# Foot_Contact_Switch_2020-11-27_13-26-25.net
KiCad netlist of a schematic drawn in EasyEDA
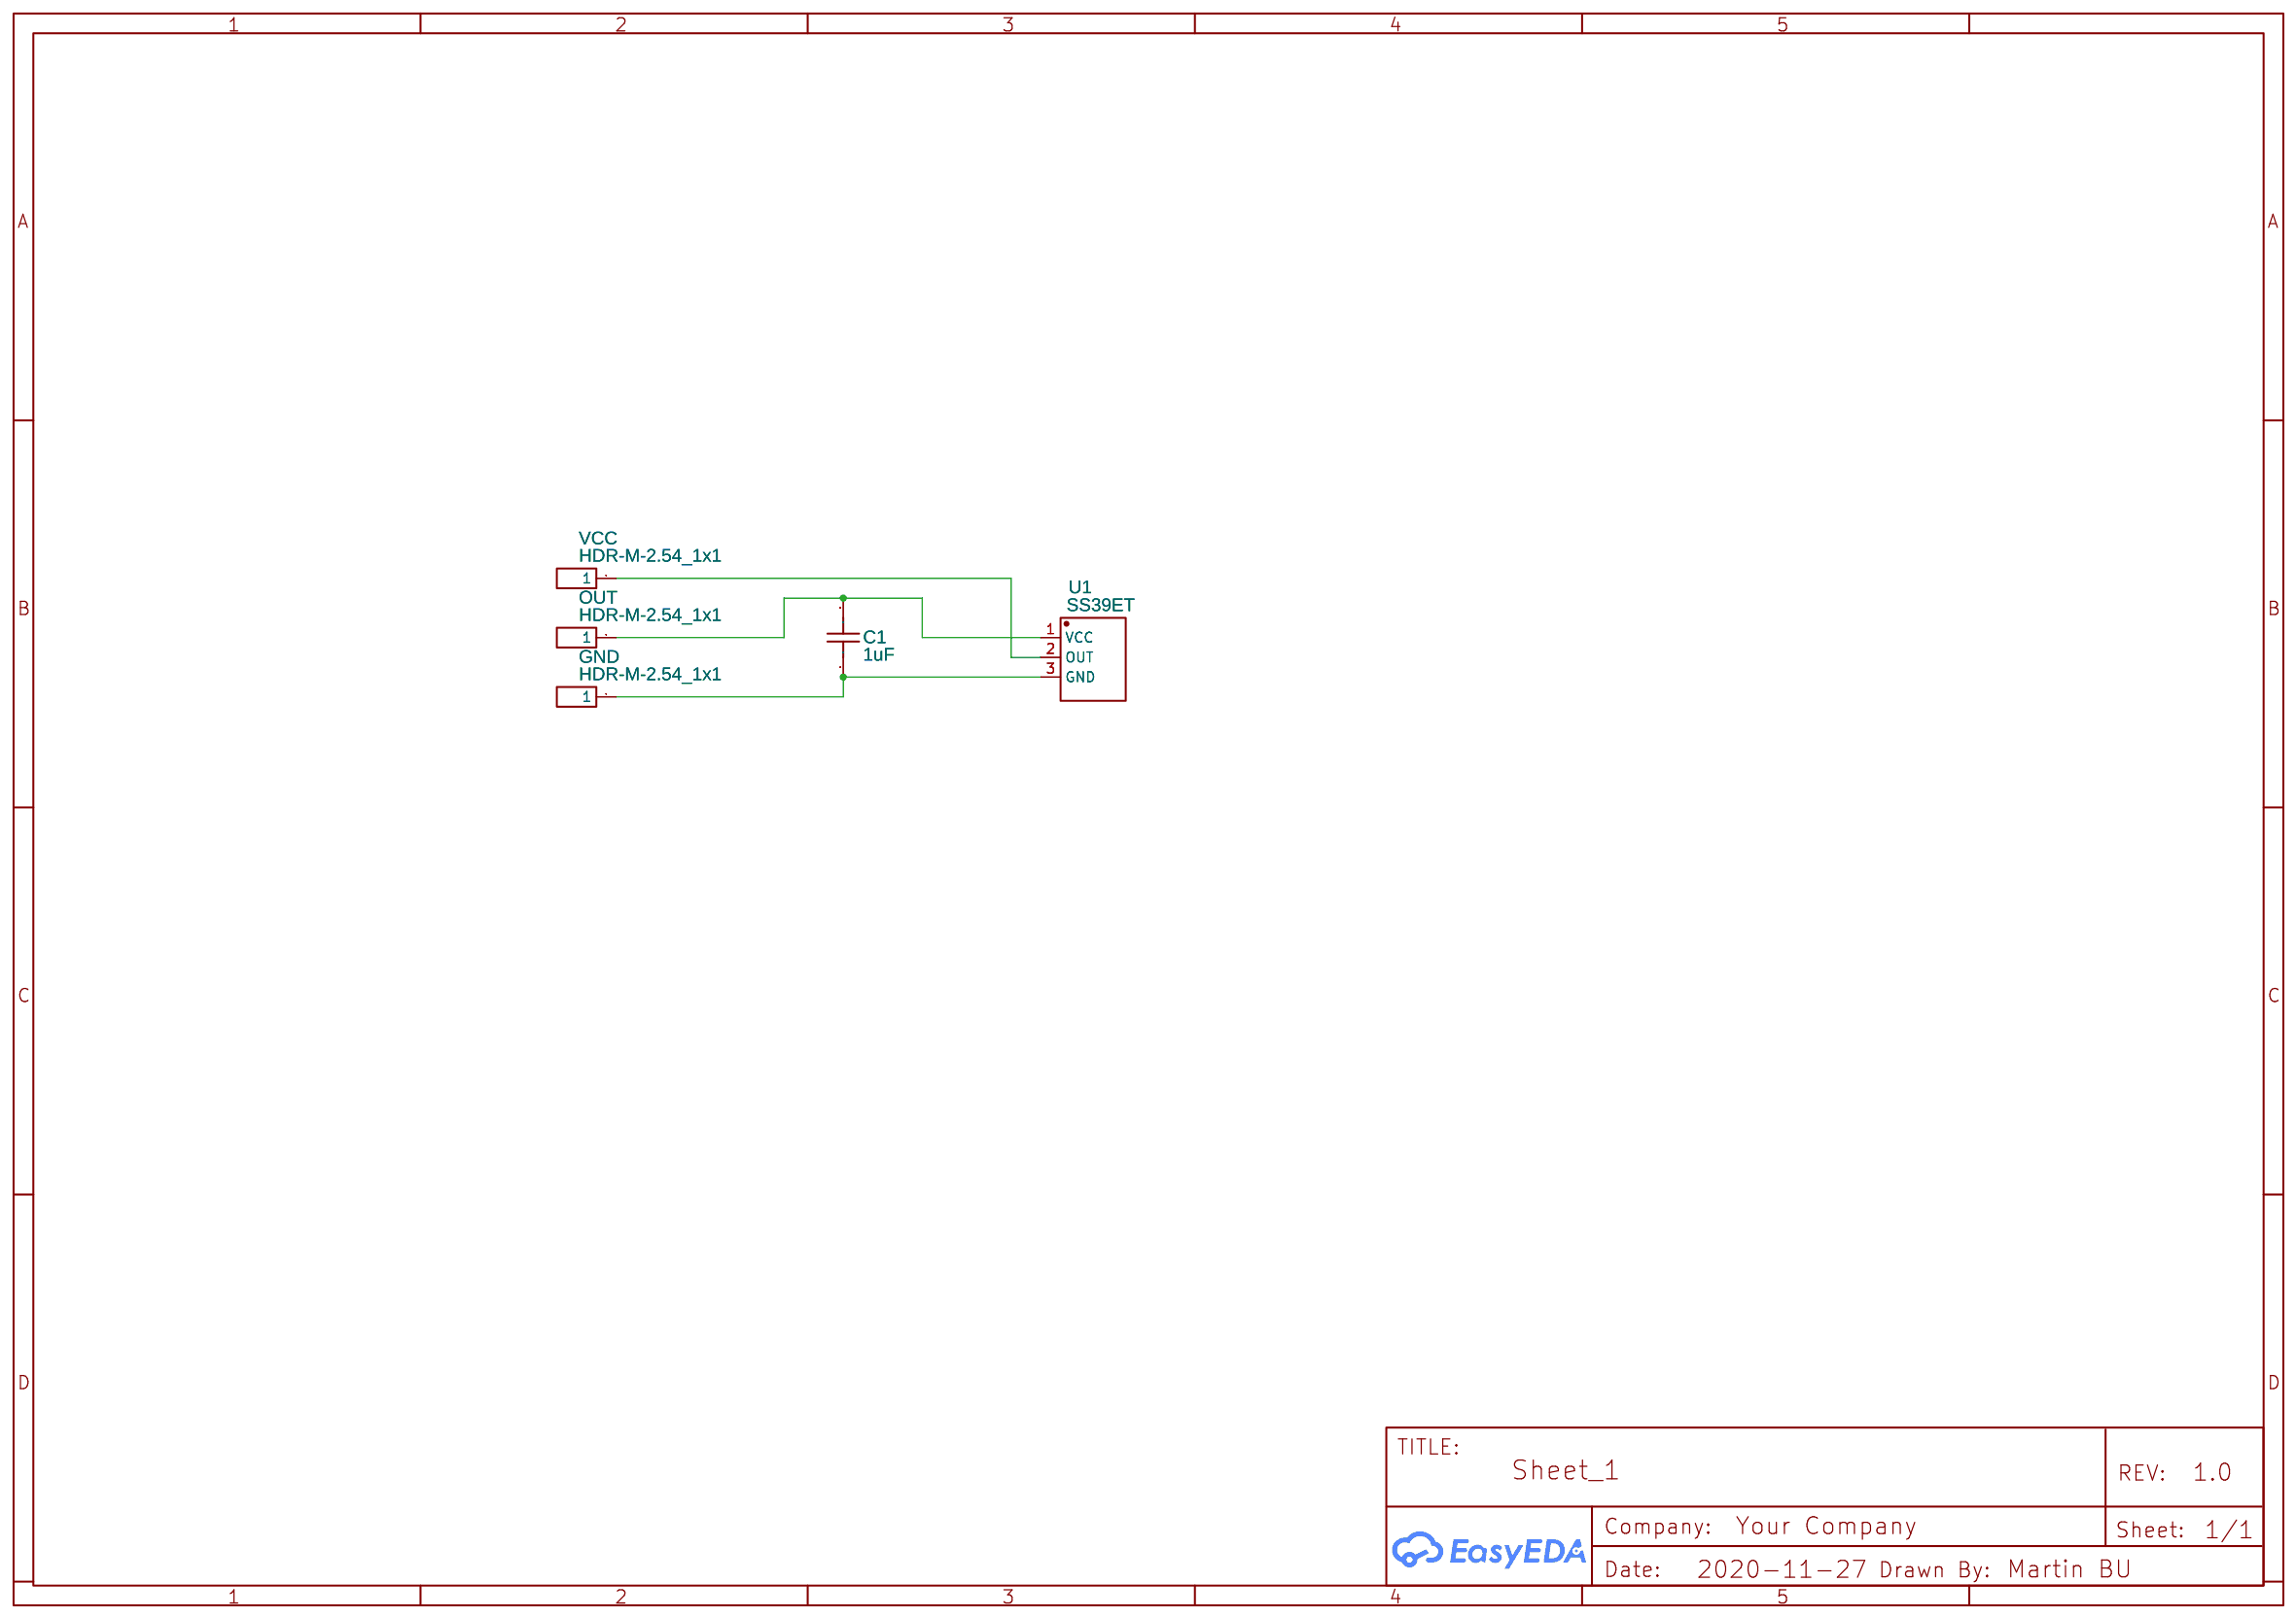
[diagram p0: schematic sheet]

(export (version "E")
  (design (tool "Eeschema 10.0.6"))
  (components
    (comp (ref "C1")
      (value "1uF")
      (fields
        (field (name "BOM_Manufacturer Part") "04026D105KAT2A")
        (field (name "BOM_Supplier Part") "C165204")
      )
      (libsource (lib "") (part "Capacitor, 1uF, 0402"))
    )
    (comp (ref "GND")
      (value "HDR-M-2.54_1x1")
      (fields (field (name "BOM_Supplier Part") "C81276"))
      (libsource (lib "") (part "HDR-M-2.54_1x1"))
    )
    (comp (ref "OUT")
      (value "HDR-M-2.54_1x1")
      (fields (field (name "BOM_Supplier Part") "C81276"))
      (libsource (lib "") (part "HDR-M-2.54_1x1_2"))
    )
    (comp (ref "U1")
      (value "SS39ET")
      (fields (field (name "BOM_Supplier Part") "C126669"))
      (libsource (lib "") (part "SS39ET"))
    )
    (comp (ref "VCC")
      (value "HDR-M-2.54_1x1")
      (fields (field (name "BOM_Supplier Part") "C81276"))
      (libsource (lib "") (part "HDR-M-2.54_1x1_1"))
    )
  )
  (nets
    (net (code "1") (name "Net-(U1-GND)") (class "Default")
      (node (ref "C1") (pin "1") (pinfunction "1_1") (pintype "unspecified"))
      (node (ref "GND") (pin "1") (pinfunction "1_1") (pintype "input"))
      (node (ref "U1") (pin "3") (pinfunction "GND_3") (pintype "unspecified"))
    )
    (net (code "2") (name "Net-(U1-OUT)") (class "Default")
      (node (ref "U1") (pin "2") (pinfunction "OUT_2") (pintype "unspecified"))
      (node (ref "VCC") (pin "1") (pinfunction "1_1") (pintype "input"))
    )
    (net (code "3") (name "Net-(U1-VCC)") (class "Default")
      (node (ref "C1") (pin "2") (pinfunction "2_2") (pintype "unspecified"))
      (node (ref "OUT") (pin "1") (pinfunction "1_1") (pintype "input"))
      (node (ref "U1") (pin "1") (pinfunction "VCC_1") (pintype "unspecified"))
    )
  )
)
